# LIMIT-INTERFACE.net
KiCad netlist of a schematic drawn in EAGLE
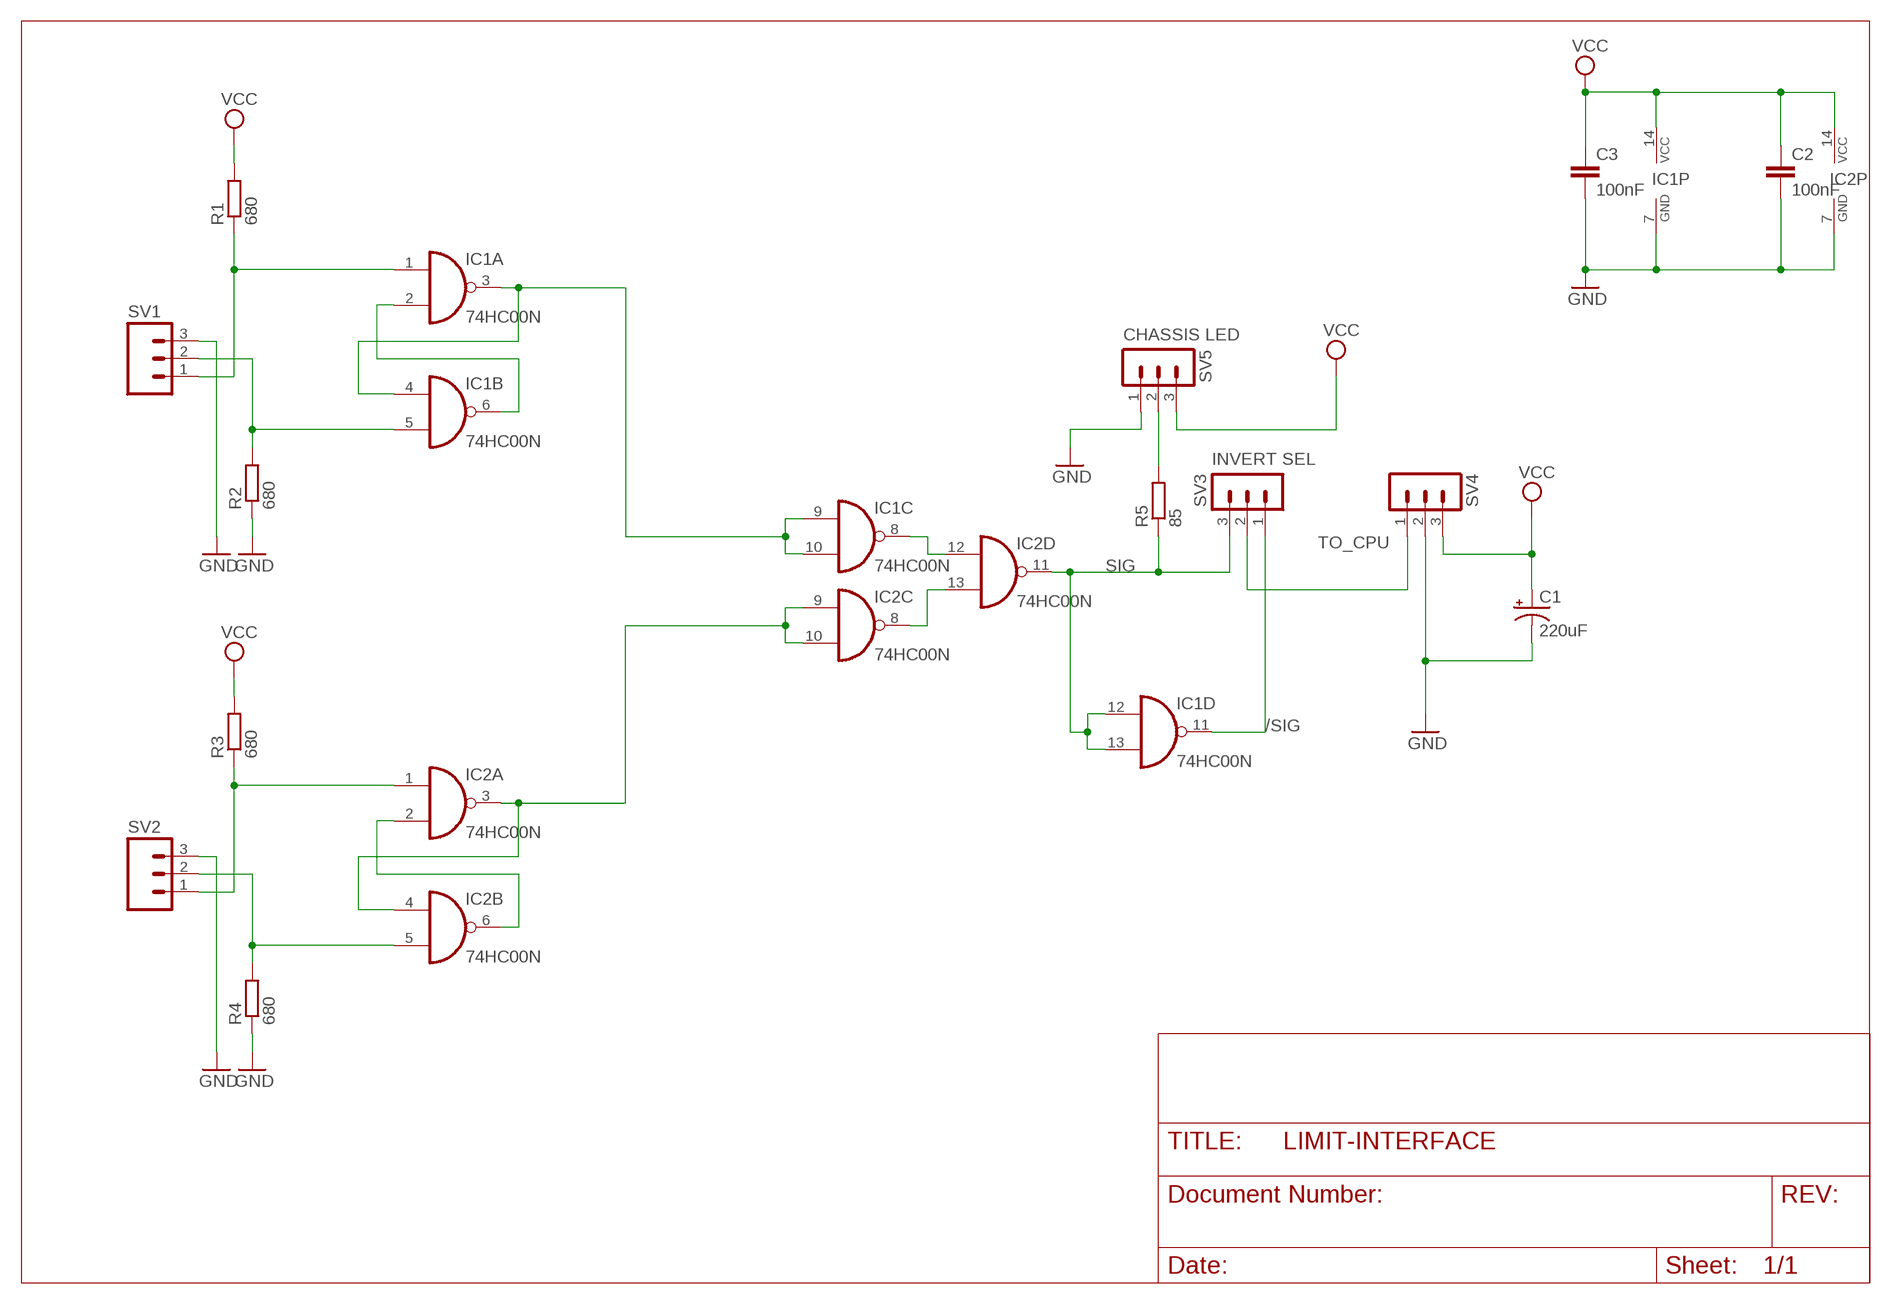
[diagram p0: schematic, sheet 1]

(export (version "E")
  (design (tool "Eeschema 10.0.6"))
  (components
    (comp (ref "C1")
      (value "220uF")
      (footprint "eagle-import:CPOL-RADIAL-1000UF-25V")
      (libsource (lib "eagle-import") (part "CAP_POLPTH4"))
    )
    (comp (ref "C2")
      (value "100nF")
      (footprint "eagle-import:CAP-PTH-SMALL")
      (libsource (lib "eagle-import") (part "CAPPTH"))
    )
    (comp (ref "C3")
      (value "100nF")
      (footprint "eagle-import:CAP-PTH-SMALL")
      (libsource (lib "eagle-import") (part "CAPPTH"))
    )
    (comp (ref "IC1")
      (value "74HC00N")
      (footprint "eagle-import:DIL14")
      (libsource (lib "eagle-import") (part "7400NHC"))
    )
    (comp (ref "IC2")
      (value "74HC00N")
      (footprint "eagle-import:DIL14")
      (libsource (lib "eagle-import") (part "7400NHC"))
    )
    (comp (ref "R1")
      (value "680")
      (footprint "eagle-import:0207_7")
      (libsource (lib "eagle-import") (part "R-EU_0207/7"))
    )
    (comp (ref "R2")
      (value "680")
      (footprint "eagle-import:0207_5V")
      (libsource (lib "eagle-import") (part "R-EU_0207/5V"))
    )
    (comp (ref "R3")
      (value "680")
      (footprint "eagle-import:0207_7")
      (libsource (lib "eagle-import") (part "R-EU_0207/7"))
    )
    (comp (ref "R4")
      (value "680")
      (footprint "eagle-import:0207_5V")
      (libsource (lib "eagle-import") (part "R-EU_0207/5V"))
    )
    (comp (ref "R5")
      (value "85")
      (footprint "eagle-import:0207_10")
      (libsource (lib "eagle-import") (part "R-EU_0207/10"))
    )
    (comp (ref "SV1")
      (value "M03-SCREW-5MM")
      (footprint "eagle-import:SCREWTERMINAL-5MM-3")
      (libsource (lib "eagle-import") (part "M03-SCREW-5MM"))
    )
    (comp (ref "SV2")
      (value "M03-SCREW-5MM")
      (footprint "eagle-import:SCREWTERMINAL-5MM-3")
      (libsource (lib "eagle-import") (part "M03-SCREW-5MM"))
    )
    (comp (ref "SV3")
      (value "MA03-1")
      (footprint "eagle-import:MA03-1")
      (libsource (lib "eagle-import") (part "MA03-1"))
    )
    (comp (ref "SV4")
      (value "MA03-1")
      (footprint "eagle-import:MA03-1")
      (libsource (lib "eagle-import") (part "MA03-1"))
    )
    (comp (ref "SV5")
      (value "MA03-1")
      (footprint "eagle-import:MA03-1")
      (libsource (lib "eagle-import") (part "MA03-1"))
    )
  )
  (nets
    (net (code "1") (name "/SIG") (class "Default")
      (node (ref "IC1") (pin "12") (pinfunction "I0_12") (pintype "input"))
      (node (ref "IC1") (pin "13") (pinfunction "I1_13") (pintype "input"))
      (node (ref "IC2") (pin "11") (pinfunction "O_11") (pintype "output"))
      (node (ref "R5") (pin "1") (pinfunction "1_1") (pintype "passive"))
      (node (ref "SV3") (pin "3") (pinfunction "3_3") (pintype "passive"))
    )
    (net (code "2") (name "/TO_CPU") (class "Default")
      (node (ref "SV3") (pin "2") (pinfunction "2_2") (pintype "passive"))
      (node (ref "SV4") (pin "1") (pinfunction "1_1") (pintype "passive"))
    )
    (net (code "3") (name "/{slash}SIG") (class "Default")
      (node (ref "IC1") (pin "11") (pinfunction "O_11") (pintype "output"))
      (node (ref "SV3") (pin "1") (pinfunction "1_1") (pintype "passive"))
    )
    (net (code "4") (name "GND") (class "Default")
      (node (ref "C1") (pin "2") (pinfunction "-_2") (pintype "passive"))
      (node (ref "C2") (pin "2") (pinfunction "2_2") (pintype "passive"))
      (node (ref "C3") (pin "2") (pinfunction "2_2") (pintype "passive"))
      (node (ref "IC1") (pin "7") (pinfunction "GND_7") (pintype "power_in"))
      (node (ref "IC2") (pin "7") (pinfunction "GND_7") (pintype "power_in"))
      (node (ref "R2") (pin "1") (pinfunction "1_1") (pintype "passive"))
      (node (ref "R4") (pin "1") (pinfunction "1_1") (pintype "passive"))
      (node (ref "SV1") (pin "3") (pinfunction "3_3") (pintype "passive"))
      (node (ref "SV2") (pin "3") (pinfunction "3_3") (pintype "passive"))
      (node (ref "SV4") (pin "2") (pinfunction "2_2") (pintype "passive"))
      (node (ref "SV5") (pin "1") (pinfunction "1_1") (pintype "passive"))
    )
    (net (code "5") (name "Net-(IC1A-I0)") (class "Default")
      (node (ref "IC1") (pin "1") (pinfunction "I0_1") (pintype "input"))
      (node (ref "R1") (pin "1") (pinfunction "1_1") (pintype "passive"))
      (node (ref "SV1") (pin "1") (pinfunction "1_1") (pintype "passive"))
    )
    (net (code "6") (name "Net-(IC1A-I1)") (class "Default")
      (node (ref "IC1") (pin "2") (pinfunction "I1_2") (pintype "input"))
      (node (ref "IC1") (pin "6") (pinfunction "O_6") (pintype "output"))
    )
    (net (code "7") (name "Net-(IC1A-O)") (class "Default")
      (node (ref "IC1") (pin "10") (pinfunction "I1_10") (pintype "input"))
      (node (ref "IC1") (pin "3") (pinfunction "O_3") (pintype "output"))
      (node (ref "IC1") (pin "4") (pinfunction "I0_4") (pintype "input"))
      (node (ref "IC1") (pin "9") (pinfunction "I0_9") (pintype "input"))
    )
    (net (code "8") (name "Net-(IC1B-I1)") (class "Default")
      (node (ref "IC1") (pin "5") (pinfunction "I1_5") (pintype "input"))
      (node (ref "R2") (pin "2") (pinfunction "2_2") (pintype "passive"))
      (node (ref "SV1") (pin "2") (pinfunction "2_2") (pintype "passive"))
    )
    (net (code "9") (name "Net-(IC1C-O)") (class "Default")
      (node (ref "IC1") (pin "8") (pinfunction "O_8") (pintype "output"))
      (node (ref "IC2") (pin "12") (pinfunction "I0_12") (pintype "input"))
    )
    (net (code "10") (name "Net-(IC2A-I0)") (class "Default")
      (node (ref "IC2") (pin "1") (pinfunction "I0_1") (pintype "input"))
      (node (ref "R3") (pin "1") (pinfunction "1_1") (pintype "passive"))
      (node (ref "SV2") (pin "1") (pinfunction "1_1") (pintype "passive"))
    )
    (net (code "11") (name "Net-(IC2A-I1)") (class "Default")
      (node (ref "IC2") (pin "2") (pinfunction "I1_2") (pintype "input"))
      (node (ref "IC2") (pin "6") (pinfunction "O_6") (pintype "output"))
    )
    (net (code "12") (name "Net-(IC2A-O)") (class "Default")
      (node (ref "IC2") (pin "10") (pinfunction "I1_10") (pintype "input"))
      (node (ref "IC2") (pin "3") (pinfunction "O_3") (pintype "output"))
      (node (ref "IC2") (pin "4") (pinfunction "I0_4") (pintype "input"))
      (node (ref "IC2") (pin "9") (pinfunction "I0_9") (pintype "input"))
    )
    (net (code "13") (name "Net-(IC2B-I1)") (class "Default")
      (node (ref "IC2") (pin "5") (pinfunction "I1_5") (pintype "input"))
      (node (ref "R4") (pin "2") (pinfunction "2_2") (pintype "passive"))
      (node (ref "SV2") (pin "2") (pinfunction "2_2") (pintype "passive"))
    )
    (net (code "14") (name "Net-(IC2C-O)") (class "Default")
      (node (ref "IC2") (pin "13") (pinfunction "I1_13") (pintype "input"))
      (node (ref "IC2") (pin "8") (pinfunction "O_8") (pintype "output"))
    )
    (net (code "15") (name "Net-(R5-Pad2)") (class "Default")
      (node (ref "R5") (pin "2") (pinfunction "2_2") (pintype "passive"))
      (node (ref "SV5") (pin "2") (pinfunction "2_2") (pintype "passive"))
    )
    (net (code "16") (name "VCC") (class "Default")
      (node (ref "C1") (pin "1") (pinfunction "+_1") (pintype "passive"))
      (node (ref "C2") (pin "1") (pinfunction "1_1") (pintype "passive"))
      (node (ref "C3") (pin "1") (pinfunction "1_1") (pintype "passive"))
      (node (ref "IC1") (pin "14") (pinfunction "VCC_14") (pintype "power_in"))
      (node (ref "IC2") (pin "14") (pinfunction "VCC_14") (pintype "power_in"))
      (node (ref "R1") (pin "2") (pinfunction "2_2") (pintype "passive"))
      (node (ref "R3") (pin "2") (pinfunction "2_2") (pintype "passive"))
      (node (ref "SV4") (pin "3") (pinfunction "3_3") (pintype "passive"))
      (node (ref "SV5") (pin "3") (pinfunction "3_3") (pintype "passive"))
    )
  )
)
